# 5V_Isolated_Power_Supply.net
KiCad netlist of a schematic drawn in Altium Designer
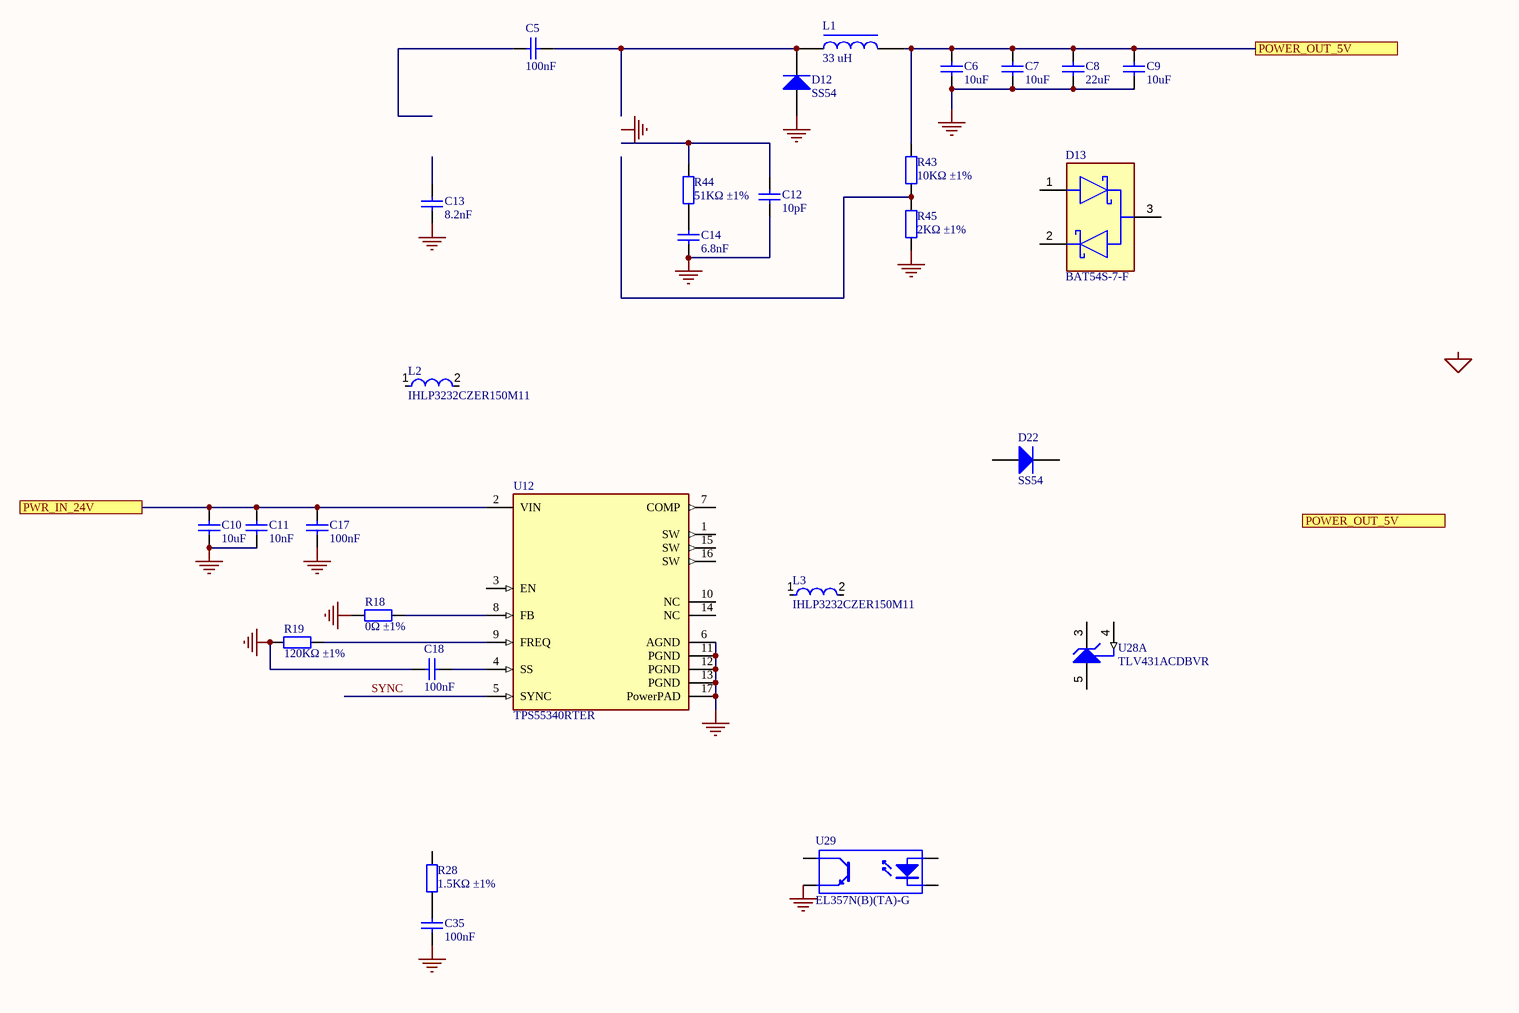
[diagram p0: 5V_Isolated_Power_Supply.SchDoc]

(export (version "E")
  (design (tool "Eeschema 10.0.6"))
  (components
    (comp (ref "C5")
      (value "100nF")
      (footprint "0603_C")
      (description "Chip capacitors")
      (fields (field (name "MANUFACTURER") "YAGEO") (field (name "PARTNUMBER") "CC0603KRX7R9BB104"))
      (libsource (lib "Cap") (part "0603 100nF (104) 10% 50V"))
    )
    (comp (ref "C6")
      (value "10uF")
      (footprint "0603_C")
      (description "Chip capacitors")
      (fields
        (field (name "MANUFACTURER") "Samsung Electro-Mechanics")
        (field (name "PARTNUMBER") "CL10A106KP8NNNC")
      )
      (libsource (lib "Cap") (part "0603 10uF (106) 10% 10V"))
    )
    (comp (ref "C7")
      (value "10uF")
      (footprint "0603_C")
      (description "Chip capacitors")
      (fields
        (field (name "MANUFACTURER") "Samsung Electro-Mechanics")
        (field (name "PARTNUMBER") "CL10A106KP8NNNC")
      )
      (libsource (lib "Cap") (part "0603 10uF (106) 10% 10V"))
    )
    (comp (ref "C8")
      (value "22uF")
      (footprint "0805_C")
      (description "Chip capacitors")
      (fields
        (field (name "MANUFACTURER") "Samsung Electro-Mechanics")
        (field (name "PARTNUMBER") "CL21A226MAQNNNE")
      )
      (libsource (lib "Cap") (part "0805 22uF (226) 20% 25V"))
    )
    (comp (ref "C9")
      (value "10uF")
      (footprint "0603_C")
      (description "Chip capacitors")
      (fields
        (field (name "MANUFACTURER") "Samsung Electro-Mechanics")
        (field (name "PARTNUMBER") "CL10A106KP8NNNC")
      )
      (libsource (lib "Cap") (part "0603 10uF (106) 10% 10V"))
    )
    (comp (ref "C10")
      (value "10uF")
      (footprint "1206_C")
      (description "Chip capacitors")
      (fields
        (field (name "MANUFACTURER") "Samsung Electro-Mechanics")
        (field (name "PARTNUMBER") "CL31A106KBHNNNE")
      )
      (libsource (lib "Cap") (part "1206 10uF (106) 10% 50V"))
    )
    (comp (ref "C11")
      (value "10nF")
      (footprint "0402_C")
      (description "Chip capacitors")
      (fields
        (field (name "MANUFACTURER") "Samsung Electro-Mechanics")
        (field (name "PARTNUMBER") "CL05B103KB5NNNC")
      )
      (libsource (lib "Cap") (part "0402 10nF (103) 10% 50V"))
    )
    (comp (ref "C12")
      (value "10pF")
      (footprint "0402_C")
      (description "Chip capacitors")
      (fields
        (field (name "MANUFACTURER") "Samsung Electro-Mechanics")
        (field (name "PARTNUMBER") "CL05C100JB5NNNC")
      )
      (libsource (lib "Cap") (part "0402 10pF (100) 5% 50V"))
    )
    (comp (ref "C13")
      (value "8.2nF")
      (footprint "0603_C")
      (description "Chip capacitors")
      (fields
        (field (name "MANUFACTURER") "Samsung Electro-Mechanics")
        (field (name "PARTNUMBER") "CL10B822KB8NNNC")
      )
      (libsource (lib "Cap") (part "0603 8.2nF (822) 10% 50V"))
    )
    (comp (ref "C14")
      (value "6.8nF")
      (footprint "0402_C")
      (description "Chip capacitors")
      (fields
        (field (name "MANUFACTURER") "Guangdong Fenghua Advanced Tech")
        (field (name "PARTNUMBER") "0402B682K500NT")
      )
      (libsource (lib "Cap") (part "0402 6.8nF (682) 10% 50V"))
    )
    (comp (ref "C17")
      (value "100nF")
      (footprint "0603_C")
      (description "Chip capacitors")
      (fields (field (name "MANUFACTURER") "YAGEO") (field (name "PARTNUMBER") "CC0603KRX7R9BB104"))
      (libsource (lib "Cap") (part "0603 100nF (104) 10% 50V"))
    )
    (comp (ref "C18")
      (value "100nF")
      (footprint "0603_C")
      (description "Chip capacitors")
      (fields (field (name "MANUFACTURER") "YAGEO") (field (name "PARTNUMBER") "CC0603KRX7R9BB104"))
      (libsource (lib "Cap") (part "0603 100nF (104) 10% 50V"))
    )
    (comp (ref "C35")
      (value "100nF")
      (footprint "0603_C")
      (description "Chip capacitors")
      (fields (field (name "MANUFACTURER") "YAGEO") (field (name "PARTNUMBER") "CC0603KRX7R9BB104"))
      (libsource (lib "Cap") (part "0603 100nF (104) 10% 50V"))
    )
    (comp (ref "D12")
      (value "SS54")
      (footprint "SMA(DO-214AC)_S1")
      (description "二极管")
      (libsource (lib "Diode") (part "SMA(DO-214AC) SS54"))
    )
    (comp (ref "D13")
      (value "BAT54S-7-F")
      (footprint "FP-SOT23-MFG")
      (description "DIODE ARRAY SCHOTTKY 30V SOT23-3")
      (libsource (lib "Altium Content Vault") (part "835e4e71cf852b8cae3cf70bf14abf8"))
    )
    (comp (ref "D22")
      (value "SS54")
      (footprint "SMA(DO-214AC)_S1")
      (description "40V 5A 550mV @ 5A SMA(DO-214AC) Schottky Barrier Diodes (SBD) ROHS")
      (libsource (lib "Diode") (part "SMA(DO-214AC) SS54"))
    )
    (comp (ref "L1")
      (value "33 uH")
      (footprint "INDPM7366X300N")
      (description "33uH ±20% 2A 270mΩ SMD,6.6x7.3x3.0mm Power Inductors RoHS")
      (libsource (lib "IUD") (part "1206 10uH 10%"))
    )
    (comp (ref "L2")
      (value "IHLP3232CZER150M11")
      (footprint "FP-IHLP-3232CZ-FP_2_413x5-MFG")
      (description "Commercial Inductors, Low DCR Series 15uH 4.3A 85.3mΩ 20%")
      (fields (field (name "TOLERANCE") "20%"))
      (libsource (lib "Altium Content Vault") (part "725321dda6339637d4d059423bc1c3c"))
    )
    (comp (ref "L3")
      (value "IHLP3232CZER150M11")
      (footprint "FP-IHLP-3232CZ-FP_2_413x5-MFG")
      (description "Commercial Inductors, Low DCR Series 15uH 4.3A 85.3mΩ 20%")
      (fields (field (name "TOLERANCE") "20%"))
      (libsource (lib "Altium Content Vault") (part "725321dda6339637d4d059423bc1c3c"))
    )
    (comp (ref "R18")
      (value "0Ω ±1%")
      (footprint "0402_R")
      (description "Chip resistor")
      (fields (field (name "POWER") "1/16W") (field (name "MANUFACTURER") "Uniroyal Elec"))
      (libsource (lib "RES") (part "0402 0R (0R0) 1%"))
    )
    (comp (ref "R19")
      (value "120KΩ ±1%")
      (footprint "0402_R")
      (description "Chip resistor")
      (fields (field (name "MANUFACTURER") "Uniroyal Elec") (field (name "PARTNUMBER") "0402WGF1203TCE"))
      (libsource (lib "RES") (part "0402 120K (1203) 1%"))
    )
    (comp (ref "R28")
      (value "1.5KΩ ±1%")
      (footprint "0402_R")
      (description "Chip resistor")
      (fields (field (name "MANUFACTURER") "Uniroyal Elec") (field (name "PARTNUMBER") "0402WGF1501TCE"))
      (libsource (lib "RES") (part "0402 1.5K (1501) 1%"))
    )
    (comp (ref "R43")
      (value "10KΩ ±1%")
      (footprint "0402_R")
      (description "Chip resistor")
      (fields (field (name "MANUFACTURER") "Uniroyal Elec") (field (name "PARTNUMBER") "0402WGF1002TCE"))
      (libsource (lib "RES") (part "0402 10K (1002) 1%"))
    )
    (comp (ref "R44")
      (value "51KΩ ±1%")
      (footprint "0402_R")
      (description "Chip resistor")
      (fields (field (name "MANUFACTURER") "Uniroyal Elec") (field (name "PARTNUMBER") "0402WGF5102TCE"))
      (libsource (lib "RES") (part "0402 51K (5102) 1%"))
    )
    (comp (ref "R45")
      (value "2KΩ ±1%")
      (footprint "0402_R")
      (description "Chip resistor")
      (fields (field (name "MANUFACTURER") "Uniroyal Elec") (field (name "PARTNUMBER") "0402WGF2001TCE"))
      (libsource (lib "RES") (part "0402 2K (2001) 1%"))
    )
    (comp (ref "U12")
      (value "TPS55340RTER")
      (footprint "FP-RTE0016C-IPC_A")
      (description "IC REG BOOST ADJ 5.25A 16WQFN")
      (libsource (lib "Altium Content Vault") (part "97752be00374b74295015ec96ff4d5f"))
    )
    (comp (ref "U28")
      (value "TLV431ACDBVR")
      (footprint "DBV0005A_L")
      (fields (field (name "MANUFACTURER") "Texas Instruments"))
      (libsource (lib "Altium Content Vault") (part "TI-TLV431ADBV5"))
    )
    (comp (ref "U29")
      (value "EL357N(B)(TA)-G")
      (footprint "SOP-4_P2.54")
      (description "贴片光耦")
      (libsource (lib "IC") (part "EL357N(B)(TA)-G_[C6649]"))
    )
  )
  (nets
    (net (code "1") (name "/POWER_OUT_5V") (class "Default")
      (node (ref "C6") (pin "2") (pinfunction "2_2") (pintype "passive"))
      (node (ref "C7") (pin "2") (pinfunction "2_2") (pintype "passive"))
      (node (ref "C8") (pin "2") (pinfunction "2_2") (pintype "passive"))
      (node (ref "C9") (pin "2") (pinfunction "2_2") (pintype "passive"))
      (node (ref "L1") (pin "2") (pinfunction "2_2") (pintype "passive"))
      (node (ref "R43") (pin "2") (pinfunction "2_2") (pintype "passive"))
    )
    (net (code "2") (name "/PWR_IN_24V") (class "Default")
      (node (ref "C10") (pin "2") (pinfunction "2_2") (pintype "passive"))
      (node (ref "C11") (pin "2") (pinfunction "2_2") (pintype "passive"))
      (node (ref "C17") (pin "2") (pinfunction "2_2") (pintype "passive"))
      (node (ref "U12") (pin "2") (pinfunction "VIN_2") (pintype "power_in"))
    )
    (net (code "3") (name "/SYNC") (class "Default")
      (node (ref "U12") (pin "5") (pinfunction "SYNC_5") (pintype "input"))
    )
    (net (code "4") (name "GND") (class "Default")
      (node (ref "C10") (pin "1") (pinfunction "1_1") (pintype "passive"))
      (node (ref "C11") (pin "1") (pinfunction "1_1") (pintype "passive"))
      (node (ref "C12") (pin "1") (pinfunction "1_1") (pintype "passive"))
      (node (ref "C13") (pin "1") (pinfunction "1_1") (pintype "passive"))
      (node (ref "C14") (pin "1") (pinfunction "1_1") (pintype "passive"))
      (node (ref "C17") (pin "1") (pinfunction "1_1") (pintype "passive"))
      (node (ref "C18") (pin "2") (pinfunction "2_2") (pintype "passive"))
      (node (ref "C35") (pin "1") (pinfunction "1_1") (pintype "passive"))
      (node (ref "C6") (pin "1") (pinfunction "1_1") (pintype "passive"))
      (node (ref "C7") (pin "1") (pinfunction "1_1") (pintype "passive"))
      (node (ref "C8") (pin "1") (pinfunction "1_1") (pintype "passive"))
      (node (ref "C9") (pin "1") (pinfunction "1_1") (pintype "passive"))
      (node (ref "D12") (pin "1") (pinfunction "A_1") (pintype "passive"))
      (node (ref "R18") (pin "1") (pinfunction "1_1") (pintype "passive"))
      (node (ref "R19") (pin "1") (pinfunction "1_1") (pintype "passive"))
      (node (ref "R45") (pin "1") (pinfunction "1_1") (pintype "passive"))
      (node (ref "U12") (pin "11") (pinfunction "PGND_11") (pintype "power_in"))
      (node (ref "U12") (pin "12") (pinfunction "PGND_12") (pintype "power_in"))
      (node (ref "U12") (pin "13") (pinfunction "PGND_13") (pintype "power_in"))
      (node (ref "U12") (pin "17") (pinfunction "PowerPAD_17") (pintype "power_in"))
      (node (ref "U12") (pin "6") (pinfunction "AGND_6") (pintype "power_in"))
      (node (ref "U29") (pin "3") (pinfunction "E_3") (pintype "passive"))
    )
    (net (code "6") (name "Net-(C12-Pad2)") (class "Default")
      (node (ref "C12") (pin "2") (pinfunction "2_2") (pintype "passive"))
      (node (ref "R44") (pin "2") (pinfunction "2_2") (pintype "passive"))
    )
    (net (code "7") (name "Net-(C14-Pad2)") (class "Default")
      (node (ref "C14") (pin "2") (pinfunction "2_2") (pintype "passive"))
      (node (ref "R44") (pin "1") (pinfunction "1_1") (pintype "passive"))
    )
    (net (code "8") (name "Net-(C35-Pad2)") (class "Default")
      (node (ref "C35") (pin "2") (pinfunction "2_2") (pintype "passive"))
      (node (ref "R28") (pin "1") (pinfunction "1_1") (pintype "passive"))
    )
    (net (code "9") (name "Net-(D12-K)") (class "Default")
      (node (ref "C5") (pin "2") (pinfunction "2_2") (pintype "passive"))
      (node (ref "D12") (pin "2") (pinfunction "K_2") (pintype "passive"))
      (node (ref "L1") (pin "1") (pinfunction "1_1") (pintype "passive"))
    )
    (net (code "10") (name "Net-(R43-Pad1)") (class "Default")
      (node (ref "R43") (pin "1") (pinfunction "1_1") (pintype "passive"))
      (node (ref "R45") (pin "2") (pinfunction "2_2") (pintype "passive"))
    )
    (net (code "11") (name "Net-(U12-FB)") (class "Default")
      (node (ref "R18") (pin "2") (pinfunction "2_2") (pintype "passive"))
      (node (ref "U12") (pin "8") (pinfunction "FB_8") (pintype "input"))
    )
    (net (code "12") (name "Net-(U12-FREQ)") (class "Default")
      (node (ref "R19") (pin "2") (pinfunction "2_2") (pintype "passive"))
      (node (ref "U12") (pin "9") (pinfunction "FREQ_9") (pintype "input"))
    )
    (net (code "13") (name "Net-(U12-SS)") (class "Default")
      (node (ref "C18") (pin "1") (pinfunction "1_1") (pintype "passive"))
      (node (ref "U12") (pin "4") (pinfunction "SS_4") (pintype "input"))
    )
    (net (code "14") (name "unconnected-(C5-Pad1)") (class "Default")
      (node (ref "C5") (pin "1") (pinfunction "1_1") (pintype "passive"))
    )
    (net (code "15") (name "unconnected-(C13-Pad2)") (class "Default")
      (node (ref "C13") (pin "2") (pinfunction "2_2") (pintype "passive"))
    )
    (net (code "16") (name "unconnected-(D13-Pad1)") (class "Default")
      (node (ref "D13") (pin "1") (pinfunction "1_1") (pintype "passive"))
    )
    (net (code "17") (name "unconnected-(D13-Pad2)") (class "Default")
      (node (ref "D13") (pin "2") (pinfunction "2_2") (pintype "passive"))
    )
    (net (code "18") (name "unconnected-(D13-Pad3)") (class "Default")
      (node (ref "D13") (pin "3") (pinfunction "3_3") (pintype "passive"))
    )
    (net (code "19") (name "unconnected-(D22-A-Pad1)") (class "Default")
      (node (ref "D22") (pin "1") (pinfunction "A_1") (pintype "passive"))
    )
    (net (code "20") (name "unconnected-(D22-K-Pad2)") (class "Default")
      (node (ref "D22") (pin "2") (pinfunction "K_2") (pintype "passive"))
    )
    (net (code "21") (name "unconnected-(L2-Pad1)") (class "Default")
      (node (ref "L2") (pin "1") (pinfunction "1_1") (pintype "passive"))
    )
    (net (code "22") (name "unconnected-(L2-Pad2)") (class "Default")
      (node (ref "L2") (pin "2") (pinfunction "2_2") (pintype "passive"))
    )
    (net (code "23") (name "unconnected-(L3-Pad1)") (class "Default")
      (node (ref "L3") (pin "1") (pinfunction "1_1") (pintype "passive"))
    )
    (net (code "24") (name "unconnected-(L3-Pad2)") (class "Default")
      (node (ref "L3") (pin "2") (pinfunction "2_2") (pintype "passive"))
    )
    (net (code "25") (name "unconnected-(R28-Pad2)") (class "Default")
      (node (ref "R28") (pin "2") (pinfunction "2_2") (pintype "passive"))
    )
    (net (code "26") (name "unconnected-(U12-COMP-Pad7)") (class "Default")
      (node (ref "U12") (pin "7") (pinfunction "COMP_7") (pintype "output"))
    )
    (net (code "27") (name "unconnected-(U12-EN-Pad3)") (class "Default")
      (node (ref "U12") (pin "3") (pinfunction "EN_3") (pintype "input"))
    )
    (net (code "28") (name "unconnected-(U12-NC-Pad10)") (class "Default")
      (node (ref "U12") (pin "10") (pinfunction "NC_10") (pintype "passive"))
    )
    (net (code "29") (name "unconnected-(U12-NC-Pad14)") (class "Default")
      (node (ref "U12") (pin "14") (pinfunction "NC_14") (pintype "passive"))
    )
    (net (code "30") (name "unconnected-(U12-SW-Pad1)") (class "Default")
      (node (ref "U12") (pin "1") (pinfunction "SW_1") (pintype "output"))
    )
    (net (code "31") (name "unconnected-(U12-SW-Pad15)") (class "Default")
      (node (ref "U12") (pin "15") (pinfunction "SW_15") (pintype "output"))
    )
    (net (code "32") (name "unconnected-(U12-SW-Pad16)") (class "Default")
      (node (ref "U12") (pin "16") (pinfunction "SW_16") (pintype "output"))
    )
    (net (code "33") (name "unconnected-(U28A-ANODE-Pad5)") (class "Default")
      (node (ref "U28") (pin "5") (pinfunction "ANODE_5") (pintype "passive"))
    )
    (net (code "34") (name "unconnected-(U28A-CATHODE-Pad3)") (class "Default")
      (node (ref "U28") (pin "3") (pinfunction "CATHODE_3") (pintype "passive"))
    )
    (net (code "35") (name "unconnected-(U28A-REF-Pad4)") (class "Default")
      (node (ref "U28") (pin "4") (pinfunction "REF_4") (pintype "input"))
    )
    (net (code "36") (name "unconnected-(U29-A-Pad1)") (class "Default")
      (node (ref "U29") (pin "1") (pinfunction "A_1") (pintype "passive"))
    )
    (net (code "37") (name "unconnected-(U29-C-Pad4)") (class "Default")
      (node (ref "U29") (pin "4") (pinfunction "C_4") (pintype "passive"))
    )
    (net (code "38") (name "unconnected-(U29-K-Pad2)") (class "Default")
      (node (ref "U29") (pin "2") (pinfunction "K_2") (pintype "passive"))
    )
  )
)
